# design.net
KiCad netlist of a schematic drawn in Altium Designer
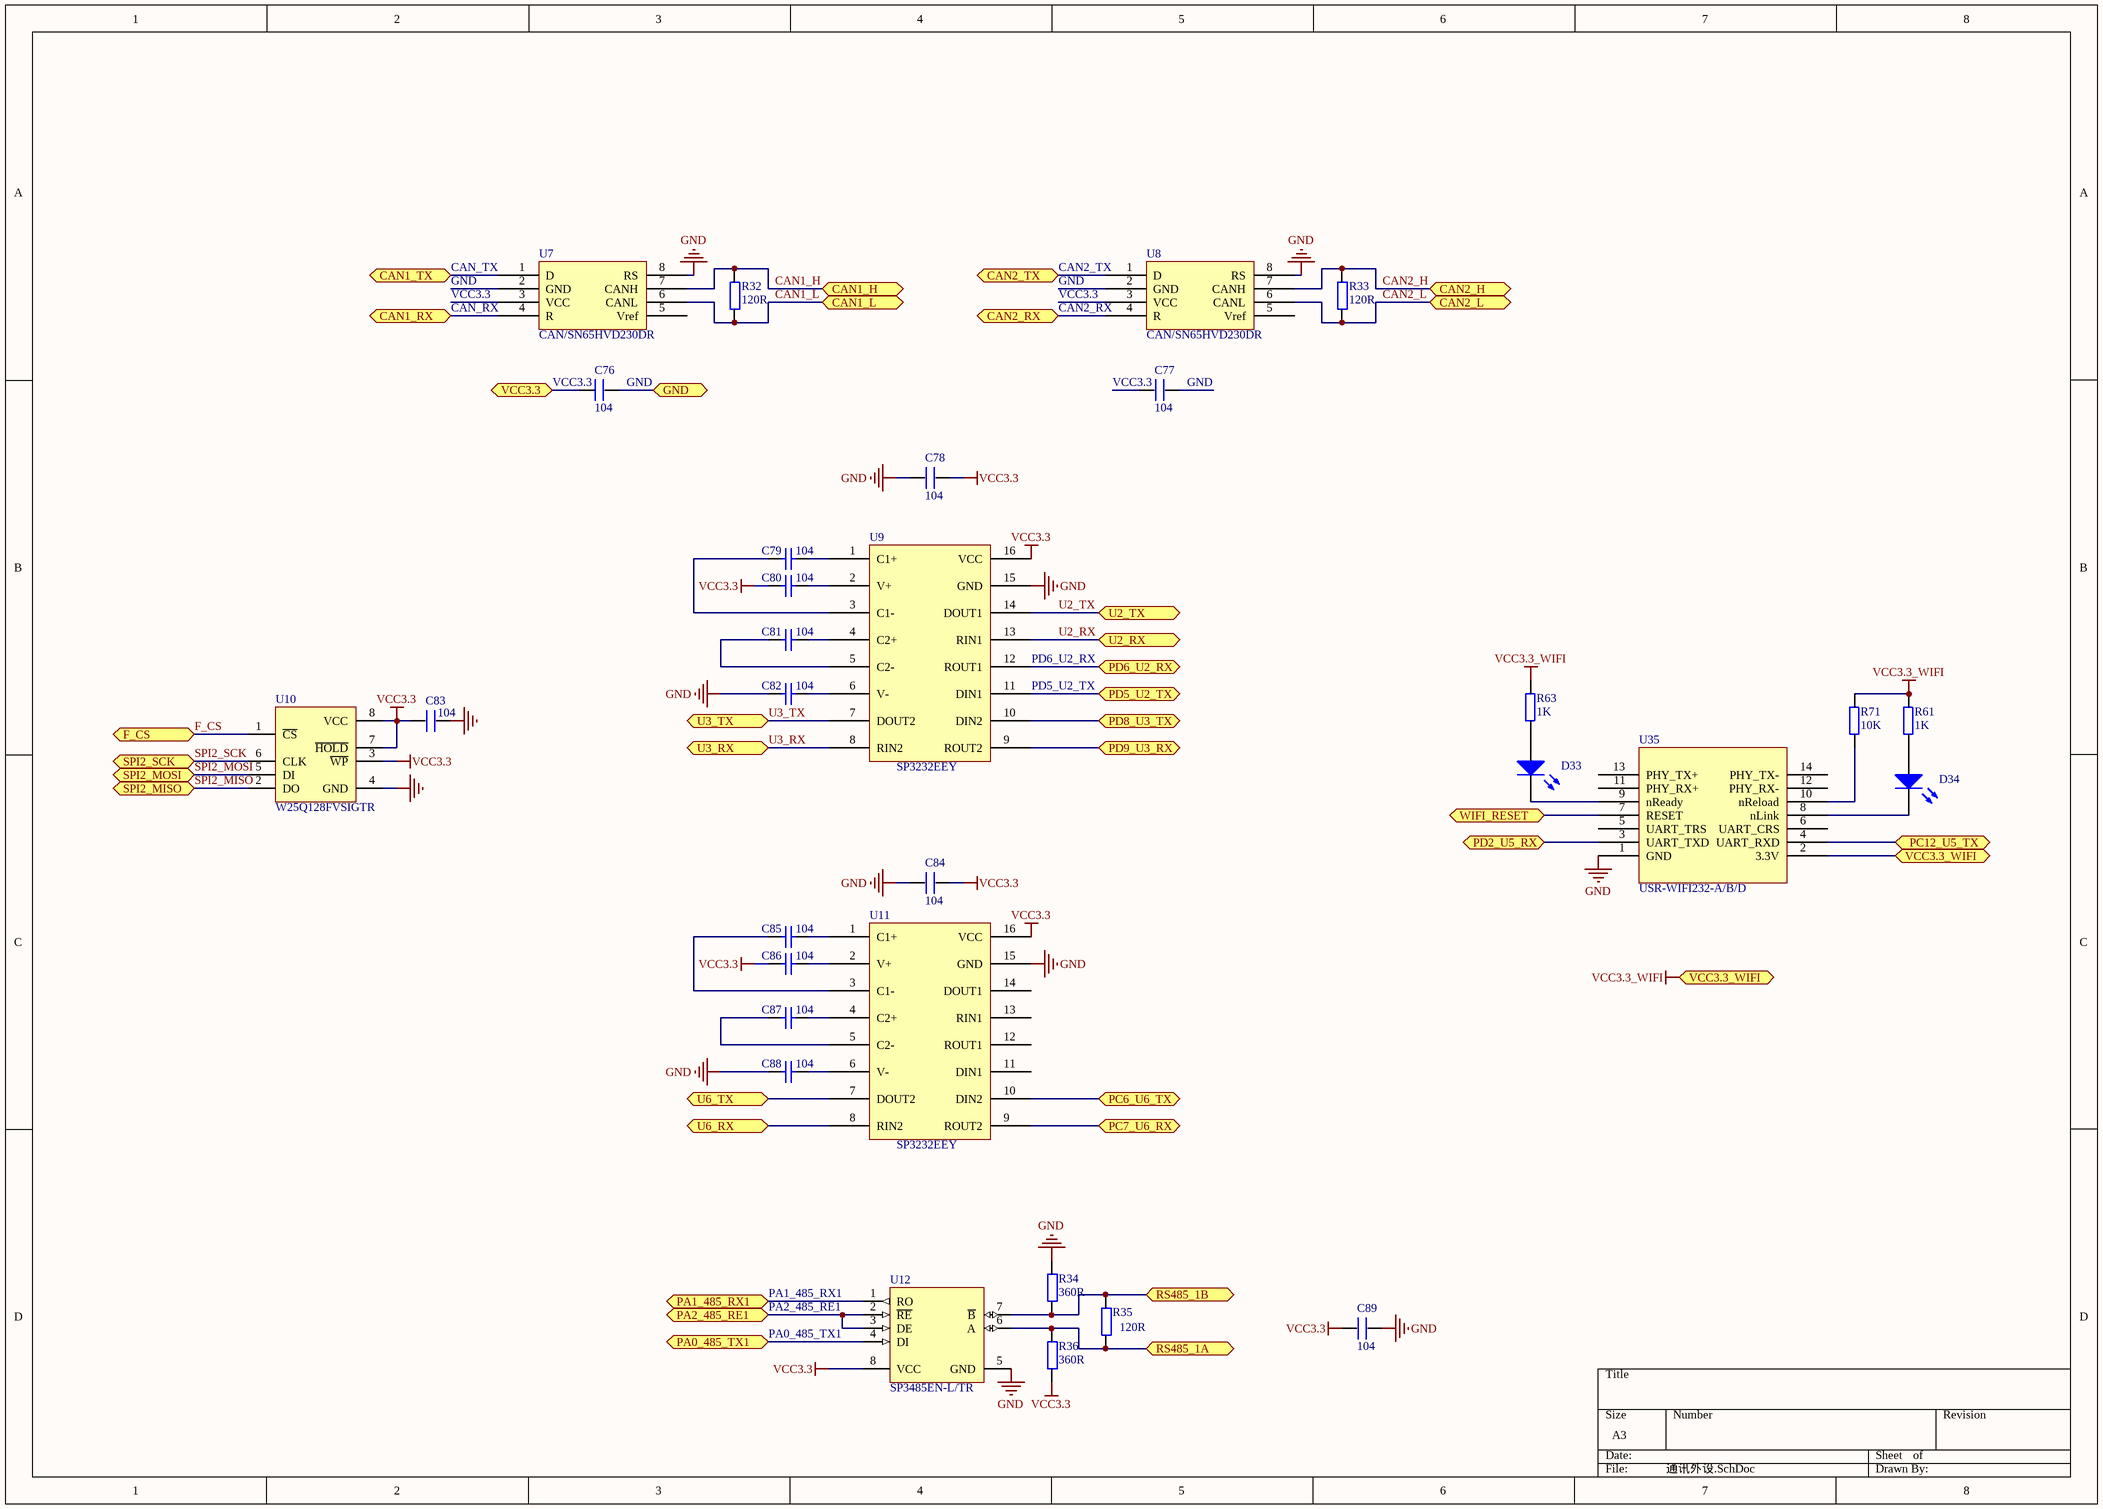
[diagram p0: 通讯外设.SchDoc]

(export (version "E")
  (design (tool "Eeschema 10.0.6"))
  (components
    (comp (ref "C76")
      (value "104")
      (footprint "0603_C")
      (libsource (lib "Explorer STM32F407封装库") (part "C_3"))
    )
    (comp (ref "C77")
      (value "104")
      (footprint "0603_C")
      (libsource (lib "Explorer STM32F407封装库") (part "C_3"))
    )
    (comp (ref "C78")
      (value "104")
      (footprint "0603_C")
      (libsource (lib "Explorer STM32F407封装库") (part "C_2"))
    )
    (comp (ref "C79")
      (value "104")
      (footprint "0603_C")
      (description "Capacitor")
      (fields (field (name "Comment") "0.1uF") (field (name "PUBLISHER") "Altium Limited"))
      (libsource (lib "Miscellaneous Devices") (part "Cap"))
    )
    (comp (ref "C80")
      (value "104")
      (footprint "0603_C")
      (description "Capacitor")
      (fields (field (name "Comment") "0.1uF") (field (name "PUBLISHER") "Altium Limited"))
      (libsource (lib "Miscellaneous Devices") (part "Cap"))
    )
    (comp (ref "C81")
      (value "104")
      (footprint "0603_C")
      (description "Capacitor")
      (fields (field (name "Comment") "0.1uF") (field (name "PUBLISHER") "Altium Limited"))
      (libsource (lib "Miscellaneous Devices") (part "Cap"))
    )
    (comp (ref "C82")
      (value "104")
      (footprint "0603_C")
      (description "Capacitor")
      (fields (field (name "Comment") "0.1uF") (field (name "PUBLISHER") "Altium Limited"))
      (libsource (lib "Miscellaneous Devices") (part "Cap"))
    )
    (comp (ref "C83") (value "104") (footprint "0603_C") (libsource (lib "WarShip V3_SCH") (part "C")))
    (comp (ref "C84")
      (value "104")
      (footprint "0603_C")
      (libsource (lib "Explorer STM32F407封装库") (part "C_2"))
    )
    (comp (ref "C85")
      (value "104")
      (footprint "0603_C")
      (description "Capacitor")
      (fields (field (name "Comment") "0.1uF") (field (name "PUBLISHER") "Altium Limited"))
      (libsource (lib "Miscellaneous Devices") (part "Cap"))
    )
    (comp (ref "C86")
      (value "104")
      (footprint "0603_C")
      (description "Capacitor")
      (fields (field (name "Comment") "0.1uF") (field (name "PUBLISHER") "Altium Limited"))
      (libsource (lib "Miscellaneous Devices") (part "Cap"))
    )
    (comp (ref "C87")
      (value "104")
      (footprint "0603_C")
      (description "Capacitor")
      (fields (field (name "Comment") "0.1uF") (field (name "PUBLISHER") "Altium Limited"))
      (libsource (lib "Miscellaneous Devices") (part "Cap"))
    )
    (comp (ref "C88")
      (value "104")
      (footprint "0603_C")
      (description "Capacitor")
      (fields (field (name "Comment") "0.1uF") (field (name "PUBLISHER") "Altium Limited"))
      (libsource (lib "Miscellaneous Devices") (part "Cap"))
    )
    (comp (ref "C89")
      (value "104")
      (footprint "0603_C")
      (libsource (lib "Explorer STM32F407封装库") (part "C_3"))
    )
    (comp (ref "D33")
      (value "红灯 0805")
      (footprint "LC-0805_LED_S1")
      (description "Typical INFRARED GaAs LED")
      (fields (field (name "PUBLISHER") "Altium Limited"))
      (libsource (lib "继电器板_1") (part "LED0"))
    )
    (comp (ref "D34")
      (value "红灯 0805")
      (footprint "LC-0805_LED_S1")
      (description "Typical INFRARED GaAs LED")
      (fields (field (name "PUBLISHER") "Altium Limited"))
      (libsource (lib "继电器板_1") (part "LED0"))
    )
    (comp (ref "R32")
      (value "120R")
      (footprint "0603_R")
      (libsource (lib "Explorer STM32F407封装库") (part "R_2"))
    )
    (comp (ref "R33")
      (value "120R")
      (footprint "0603_R")
      (libsource (lib "Explorer STM32F407封装库") (part "R_2"))
    )
    (comp (ref "R34")
      (value "360R")
      (footprint "0603_R")
      (libsource (lib "Explorer STM32F407封装库") (part "R_2"))
    )
    (comp (ref "R35")
      (value "120R")
      (footprint "0603_R")
      (libsource (lib "Explorer STM32F407封装库") (part "R_2"))
    )
    (comp (ref "R36")
      (value "360R")
      (footprint "0603_R")
      (libsource (lib "Explorer STM32F407封装库") (part "R_2"))
    )
    (comp (ref "R61")
      (value "1K")
      (footprint "0603_R")
      (libsource (lib "Explorer STM32F407封装库") (part "R_2"))
    )
    (comp (ref "R63")
      (value "1K")
      (footprint "0603_R")
      (libsource (lib "Explorer STM32F407封装库") (part "R_2"))
    )
    (comp (ref "R71")
      (value "10K")
      (footprint "0603_R")
      (libsource (lib "Explorer STM32F407封装库") (part "R_2"))
    )
    (comp (ref "U7")
      (value "CAN/SN65HVD230DR")
      (footprint "SOIC-8_150mil")
      (description "CAN")
      (libsource (lib "Miscellaneous Devices LC") (part "CAN/SN65HVD230DR"))
    )
    (comp (ref "U8")
      (value "CAN/SN65HVD230DR")
      (footprint "SOIC-8_150mil")
      (description "CAN")
      (libsource (lib "Miscellaneous Devices LC") (part "CAN/SN65HVD230DR"))
    )
    (comp (ref "U9")
      (value "SP3232EEY")
      (footprint "TSSOP-16")
      (description "RS232")
      (libsource (lib "Smart_board_v1") (part "MAX3232CUE"))
    )
    (comp (ref "U10")
      (value "W25Q128FVSIGTR")
      (footprint "SOIC8_W")
      (description "Flash ROM")
      (libsource (lib "fszhang") (part "W25QXX"))
    )
    (comp (ref "U11")
      (value "SP3232EEY")
      (footprint "TSSOP-16")
      (description "RS232")
      (libsource (lib "Smart_board_v1") (part "MAX3232CUE"))
    )
    (comp (ref "U12")
      (value "SP3485EN-L/TR")
      (footprint "SOIC-8_150mil")
      (description "RS-485/RS-422")
      (libsource (lib "Miscellaneous Devices LC") (part "SP3485EN-L/TR"))
    )
    (comp (ref "U35")
      (value "USR-WIFI232-A/B/D")
      (footprint "USR-WIFI232-A/B/D")
      (libsource (lib "USR-WIFI232-ABD-SCH") (part "USR-WIFI232-A/B/D"))
    )
  )
  (nets
    (net (code "1") (name "/CAN1_H") (class "Default")
      (node (ref "R32") (pin "2") (pintype "passive"))
      (node (ref "U7") (pin "7") (pinfunction "CANH_7") (pintype "passive"))
    )
    (net (code "2") (name "/CAN1_L") (class "Default")
      (node (ref "R32") (pin "1") (pintype "passive"))
      (node (ref "U7") (pin "6") (pinfunction "CANL_6") (pintype "passive"))
    )
    (net (code "3") (name "/CAN2_H") (class "Default")
      (node (ref "R33") (pin "2") (pintype "passive"))
      (node (ref "U8") (pin "7") (pinfunction "CANH_7") (pintype "passive"))
    )
    (net (code "4") (name "/CAN2_L") (class "Default")
      (node (ref "R33") (pin "1") (pintype "passive"))
      (node (ref "U8") (pin "6") (pinfunction "CANL_6") (pintype "passive"))
    )
    (net (code "5") (name "/CAN2_RX") (class "Default")
      (node (ref "U8") (pin "4") (pinfunction "R_4") (pintype "passive"))
    )
    (net (code "6") (name "/CAN2_TX") (class "Default")
      (node (ref "U8") (pin "1") (pinfunction "D_1") (pintype "passive"))
    )
    (net (code "7") (name "/CAN_RX") (class "Default")
      (node (ref "U7") (pin "4") (pinfunction "R_4") (pintype "passive"))
    )
    (net (code "8") (name "/CAN_TX") (class "Default")
      (node (ref "U7") (pin "1") (pinfunction "D_1") (pintype "passive"))
    )
    (net (code "9") (name "/F_CS") (class "Default")
      (node (ref "U10") (pin "1") (pinfunction "~{CS}_1") (pintype "passive"))
    )
    (net (code "10") (name "/PA0_485_TX1") (class "Default")
      (node (ref "U12") (pin "4") (pinfunction "DI_4") (pintype "input"))
    )
    (net (code "11") (name "/PA1_485_RX1") (class "Default")
      (node (ref "U12") (pin "1") (pinfunction "RO_1") (pintype "output"))
    )
    (net (code "12") (name "/PA2_485_RE1") (class "Default")
      (node (ref "U12") (pin "2") (pinfunction "~{RE}_2") (pintype "input"))
      (node (ref "U12") (pin "3") (pinfunction "DE_3") (pintype "input"))
    )
    (net (code "13") (name "/PC6_U6_TX") (class "Default")
      (node (ref "U11") (pin "10") (pinfunction "DIN2_10") (pintype "passive"))
    )
    (net (code "14") (name "/PC7_U6_RX") (class "Default")
      (node (ref "U11") (pin "9") (pinfunction "ROUT2_9") (pintype "passive"))
    )
    (net (code "15") (name "/PC12_U5_TX") (class "Default")
      (node (ref "U35") (pin "4") (pinfunction "UART_RXD_4") (pintype "passive"))
    )
    (net (code "16") (name "/PD2_U5_RX") (class "Default")
      (node (ref "U35") (pin "3") (pinfunction "UART_TXD_3") (pintype "passive"))
    )
    (net (code "17") (name "/PD5_U2_TX") (class "Default")
      (node (ref "U9") (pin "11") (pinfunction "DIN1_11") (pintype "passive"))
    )
    (net (code "18") (name "/PD6_U2_RX") (class "Default")
      (node (ref "U9") (pin "12") (pinfunction "ROUT1_12") (pintype "passive"))
    )
    (net (code "19") (name "/PD8_U3_TX") (class "Default")
      (node (ref "U9") (pin "10") (pinfunction "DIN2_10") (pintype "passive"))
    )
    (net (code "20") (name "/PD9_U3_RX") (class "Default")
      (node (ref "U9") (pin "9") (pinfunction "ROUT2_9") (pintype "passive"))
    )
    (net (code "21") (name "/RS485_1A") (class "Default")
      (node (ref "R35") (pin "1") (pintype "passive"))
      (node (ref "R36") (pin "2") (pintype "passive"))
      (node (ref "U12") (pin "6") (pinfunction "A_6") (pintype "bidirectional"))
    )
    (net (code "22") (name "/RS485_1B") (class "Default")
      (node (ref "R34") (pin "1") (pintype "passive"))
      (node (ref "R35") (pin "2") (pintype "passive"))
      (node (ref "U12") (pin "7") (pinfunction "~{B}_7") (pintype "bidirectional"))
    )
    (net (code "23") (name "/SPI2_MISO") (class "Default")
      (node (ref "U10") (pin "2") (pinfunction "DO_2") (pintype "passive"))
    )
    (net (code "24") (name "/SPI2_MOSI") (class "Default")
      (node (ref "U10") (pin "5") (pinfunction "DI_5") (pintype "passive"))
    )
    (net (code "25") (name "/SPI2_SCK") (class "Default")
      (node (ref "U10") (pin "6") (pinfunction "CLK_6") (pintype "passive"))
    )
    (net (code "26") (name "/U2_RX") (class "Default")
      (node (ref "U9") (pin "13") (pinfunction "RIN1_13") (pintype "passive"))
    )
    (net (code "27") (name "/U2_TX") (class "Default")
      (node (ref "U9") (pin "14") (pinfunction "DOUT1_14") (pintype "passive"))
    )
    (net (code "28") (name "/U3_RX") (class "Default")
      (node (ref "U9") (pin "8") (pinfunction "RIN2_8") (pintype "passive"))
    )
    (net (code "29") (name "/U3_TX") (class "Default")
      (node (ref "U9") (pin "7") (pinfunction "DOUT2_7") (pintype "passive"))
    )
    (net (code "30") (name "/U6_RX") (class "Default")
      (node (ref "U11") (pin "8") (pinfunction "RIN2_8") (pintype "passive"))
    )
    (net (code "31") (name "/U6_TX") (class "Default")
      (node (ref "U11") (pin "7") (pinfunction "DOUT2_7") (pintype "passive"))
    )
    (net (code "32") (name "/WIFI_RESET") (class "Default")
      (node (ref "U35") (pin "7") (pinfunction "RESET_7") (pintype "passive"))
    )
    (net (code "33") (name "GND") (class "Default")
      (node (ref "C76") (pin "2") (pintype "passive"))
      (node (ref "C77") (pin "2") (pintype "passive"))
      (node (ref "C78") (pin "1") (pintype "passive"))
      (node (ref "C82") (pin "2") (pinfunction "2_2") (pintype "passive"))
      (node (ref "C83") (pin "2") (pintype "passive"))
      (node (ref "C84") (pin "1") (pintype "passive"))
      (node (ref "C88") (pin "2") (pinfunction "2_2") (pintype "passive"))
      (node (ref "C89") (pin "2") (pintype "passive"))
      (node (ref "R34") (pin "2") (pintype "passive"))
      (node (ref "U10") (pin "4") (pinfunction "GND_4") (pintype "passive"))
      (node (ref "U11") (pin "15") (pinfunction "GND_15") (pintype "passive"))
      (node (ref "U12") (pin "5") (pinfunction "GND_5") (pintype "power_in"))
      (node (ref "U35") (pin "1") (pinfunction "GND_1") (pintype "passive"))
      (node (ref "U7") (pin "2") (pinfunction "GND_2") (pintype "passive"))
      (node (ref "U7") (pin "8") (pinfunction "RS_8") (pintype "passive"))
      (node (ref "U8") (pin "2") (pinfunction "GND_2") (pintype "passive"))
      (node (ref "U8") (pin "8") (pinfunction "RS_8") (pintype "passive"))
      (node (ref "U9") (pin "15") (pinfunction "GND_15") (pintype "passive"))
    )
    (net (code "34") (name "Net-(D33-PadA)") (class "Default")
      (node (ref "D33") (pin "A") (pinfunction "A_A") (pintype "passive"))
      (node (ref "R63") (pin "2") (pintype "passive"))
    )
    (net (code "35") (name "Net-(D34-PadA)") (class "Default")
      (node (ref "D34") (pin "A") (pinfunction "A_A") (pintype "passive"))
      (node (ref "R61") (pin "2") (pintype "passive"))
    )
    (net (code "36") (name "Net-(U9-C1+)") (class "Default")
      (node (ref "C79") (pin "1") (pinfunction "1_1") (pintype "passive"))
      (node (ref "U9") (pin "1") (pinfunction "C1+_1") (pintype "passive"))
    )
    (net (code "37") (name "Net-(U9-C1-)") (class "Default")
      (node (ref "C79") (pin "2") (pinfunction "2_2") (pintype "passive"))
      (node (ref "U9") (pin "3") (pinfunction "C1-_3") (pintype "passive"))
    )
    (net (code "38") (name "Net-(U9-C2+)") (class "Default")
      (node (ref "C81") (pin "1") (pinfunction "1_1") (pintype "passive"))
      (node (ref "U9") (pin "4") (pinfunction "C2+_4") (pintype "passive"))
    )
    (net (code "39") (name "Net-(U9-C2-)") (class "Default")
      (node (ref "C81") (pin "2") (pinfunction "2_2") (pintype "passive"))
      (node (ref "U9") (pin "5") (pinfunction "C2-_5") (pintype "passive"))
    )
    (net (code "40") (name "Net-(U9-V+)") (class "Default")
      (node (ref "C80") (pin "1") (pinfunction "1_1") (pintype "passive"))
      (node (ref "U9") (pin "2") (pinfunction "V+_2") (pintype "passive"))
    )
    (net (code "41") (name "Net-(U9-V-)") (class "Default")
      (node (ref "C82") (pin "1") (pinfunction "1_1") (pintype "passive"))
      (node (ref "U9") (pin "6") (pinfunction "V-_6") (pintype "passive"))
    )
    (net (code "42") (name "Net-(U11-C1+)") (class "Default")
      (node (ref "C85") (pin "1") (pinfunction "1_1") (pintype "passive"))
      (node (ref "U11") (pin "1") (pinfunction "C1+_1") (pintype "passive"))
    )
    (net (code "43") (name "Net-(U11-C1-)") (class "Default")
      (node (ref "C85") (pin "2") (pinfunction "2_2") (pintype "passive"))
      (node (ref "U11") (pin "3") (pinfunction "C1-_3") (pintype "passive"))
    )
    (net (code "44") (name "Net-(U11-C2+)") (class "Default")
      (node (ref "C87") (pin "1") (pinfunction "1_1") (pintype "passive"))
      (node (ref "U11") (pin "4") (pinfunction "C2+_4") (pintype "passive"))
    )
    (net (code "45") (name "Net-(U11-C2-)") (class "Default")
      (node (ref "C87") (pin "2") (pinfunction "2_2") (pintype "passive"))
      (node (ref "U11") (pin "5") (pinfunction "C2-_5") (pintype "passive"))
    )
    (net (code "46") (name "Net-(U11-V+)") (class "Default")
      (node (ref "C86") (pin "1") (pinfunction "1_1") (pintype "passive"))
      (node (ref "U11") (pin "2") (pinfunction "V+_2") (pintype "passive"))
    )
    (net (code "47") (name "Net-(U11-V-)") (class "Default")
      (node (ref "C88") (pin "1") (pinfunction "1_1") (pintype "passive"))
      (node (ref "U11") (pin "6") (pinfunction "V-_6") (pintype "passive"))
    )
    (net (code "48") (name "Net-(U35-nLink)") (class "Default")
      (node (ref "D34") (pin "K") (pinfunction "K_K") (pintype "passive"))
      (node (ref "U35") (pin "8") (pinfunction "nLink_8") (pintype "passive"))
    )
    (net (code "49") (name "Net-(U35-nReady)") (class "Default")
      (node (ref "D33") (pin "K") (pinfunction "K_K") (pintype "passive"))
      (node (ref "U35") (pin "9") (pinfunction "nReady_9") (pintype "passive"))
    )
    (net (code "50") (name "Net-(U35-nReload)") (class "Default")
      (node (ref "R71") (pin "2") (pintype "passive"))
      (node (ref "U35") (pin "10") (pinfunction "nReload_10") (pintype "passive"))
    )
    (net (code "51") (name "VCC3.3") (class "Default")
      (node (ref "C76") (pin "1") (pintype "passive"))
      (node (ref "C77") (pin "1") (pintype "passive"))
      (node (ref "C78") (pin "2") (pintype "passive"))
      (node (ref "C80") (pin "2") (pinfunction "2_2") (pintype "passive"))
      (node (ref "C83") (pin "1") (pintype "passive"))
      (node (ref "C84") (pin "2") (pintype "passive"))
      (node (ref "C86") (pin "2") (pinfunction "2_2") (pintype "passive"))
      (node (ref "C89") (pin "1") (pintype "passive"))
      (node (ref "R36") (pin "1") (pintype "passive"))
      (node (ref "U10") (pin "3") (pinfunction "~{WP}_3") (pintype "passive"))
      (node (ref "U10") (pin "7") (pinfunction "~{HOLD}_7") (pintype "passive"))
      (node (ref "U10") (pin "8") (pinfunction "VCC_8") (pintype "passive"))
      (node (ref "U11") (pin "16") (pinfunction "VCC_16") (pintype "passive"))
      (node (ref "U12") (pin "8") (pinfunction "VCC_8") (pintype "power_in"))
      (node (ref "U7") (pin "3") (pinfunction "VCC_3") (pintype "passive"))
      (node (ref "U8") (pin "3") (pinfunction "VCC_3") (pintype "passive"))
      (node (ref "U9") (pin "16") (pinfunction "VCC_16") (pintype "passive"))
    )
    (net (code "52") (name "VCC3.3_WIFI") (class "Default")
      (node (ref "R61") (pin "1") (pintype "passive"))
      (node (ref "R63") (pin "1") (pintype "passive"))
      (node (ref "R71") (pin "1") (pintype "passive"))
      (node (ref "U35") (pin "2") (pinfunction "3.3V_2") (pintype "passive"))
    )
    (net (code "53") (name "unconnected-(U7-Vref-Pad5)") (class "Default")
      (node (ref "U7") (pin "5") (pinfunction "Vref_5") (pintype "passive"))
    )
    (net (code "54") (name "unconnected-(U8-Vref-Pad5)") (class "Default")
      (node (ref "U8") (pin "5") (pinfunction "Vref_5") (pintype "passive"))
    )
    (net (code "55") (name "unconnected-(U11-DIN1-Pad11)") (class "Default")
      (node (ref "U11") (pin "11") (pinfunction "DIN1_11") (pintype "passive"))
    )
    (net (code "56") (name "unconnected-(U11-DOUT1-Pad14)") (class "Default")
      (node (ref "U11") (pin "14") (pinfunction "DOUT1_14") (pintype "passive"))
    )
    (net (code "57") (name "unconnected-(U11-RIN1-Pad13)") (class "Default")
      (node (ref "U11") (pin "13") (pinfunction "RIN1_13") (pintype "passive"))
    )
    (net (code "58") (name "unconnected-(U11-ROUT1-Pad12)") (class "Default")
      (node (ref "U11") (pin "12") (pinfunction "ROUT1_12") (pintype "passive"))
    )
    (net (code "59") (name "unconnected-(U35-PHY_RX+-Pad11)") (class "Default")
      (node (ref "U35") (pin "11") (pinfunction "PHY_RX+_11") (pintype "passive"))
    )
    (net (code "60") (name "unconnected-(U35-PHY_RX--Pad12)") (class "Default")
      (node (ref "U35") (pin "12") (pinfunction "PHY_RX-_12") (pintype "passive"))
    )
    (net (code "61") (name "unconnected-(U35-PHY_TX+-Pad13)") (class "Default")
      (node (ref "U35") (pin "13") (pinfunction "PHY_TX+_13") (pintype "passive"))
    )
    (net (code "62") (name "unconnected-(U35-PHY_TX--Pad14)") (class "Default")
      (node (ref "U35") (pin "14") (pinfunction "PHY_TX-_14") (pintype "passive"))
    )
    (net (code "63") (name "unconnected-(U35-UART_CRS-Pad6)") (class "Default")
      (node (ref "U35") (pin "6") (pinfunction "UART_CRS_6") (pintype "passive"))
    )
    (net (code "64") (name "unconnected-(U35-UART_TRS-Pad5)") (class "Default")
      (node (ref "U35") (pin "5") (pinfunction "UART_TRS_5") (pintype "passive"))
    )
  )
)
